# Vers_3_Moppy_Board.net
KiCad netlist of a schematic drawn in EAGLE
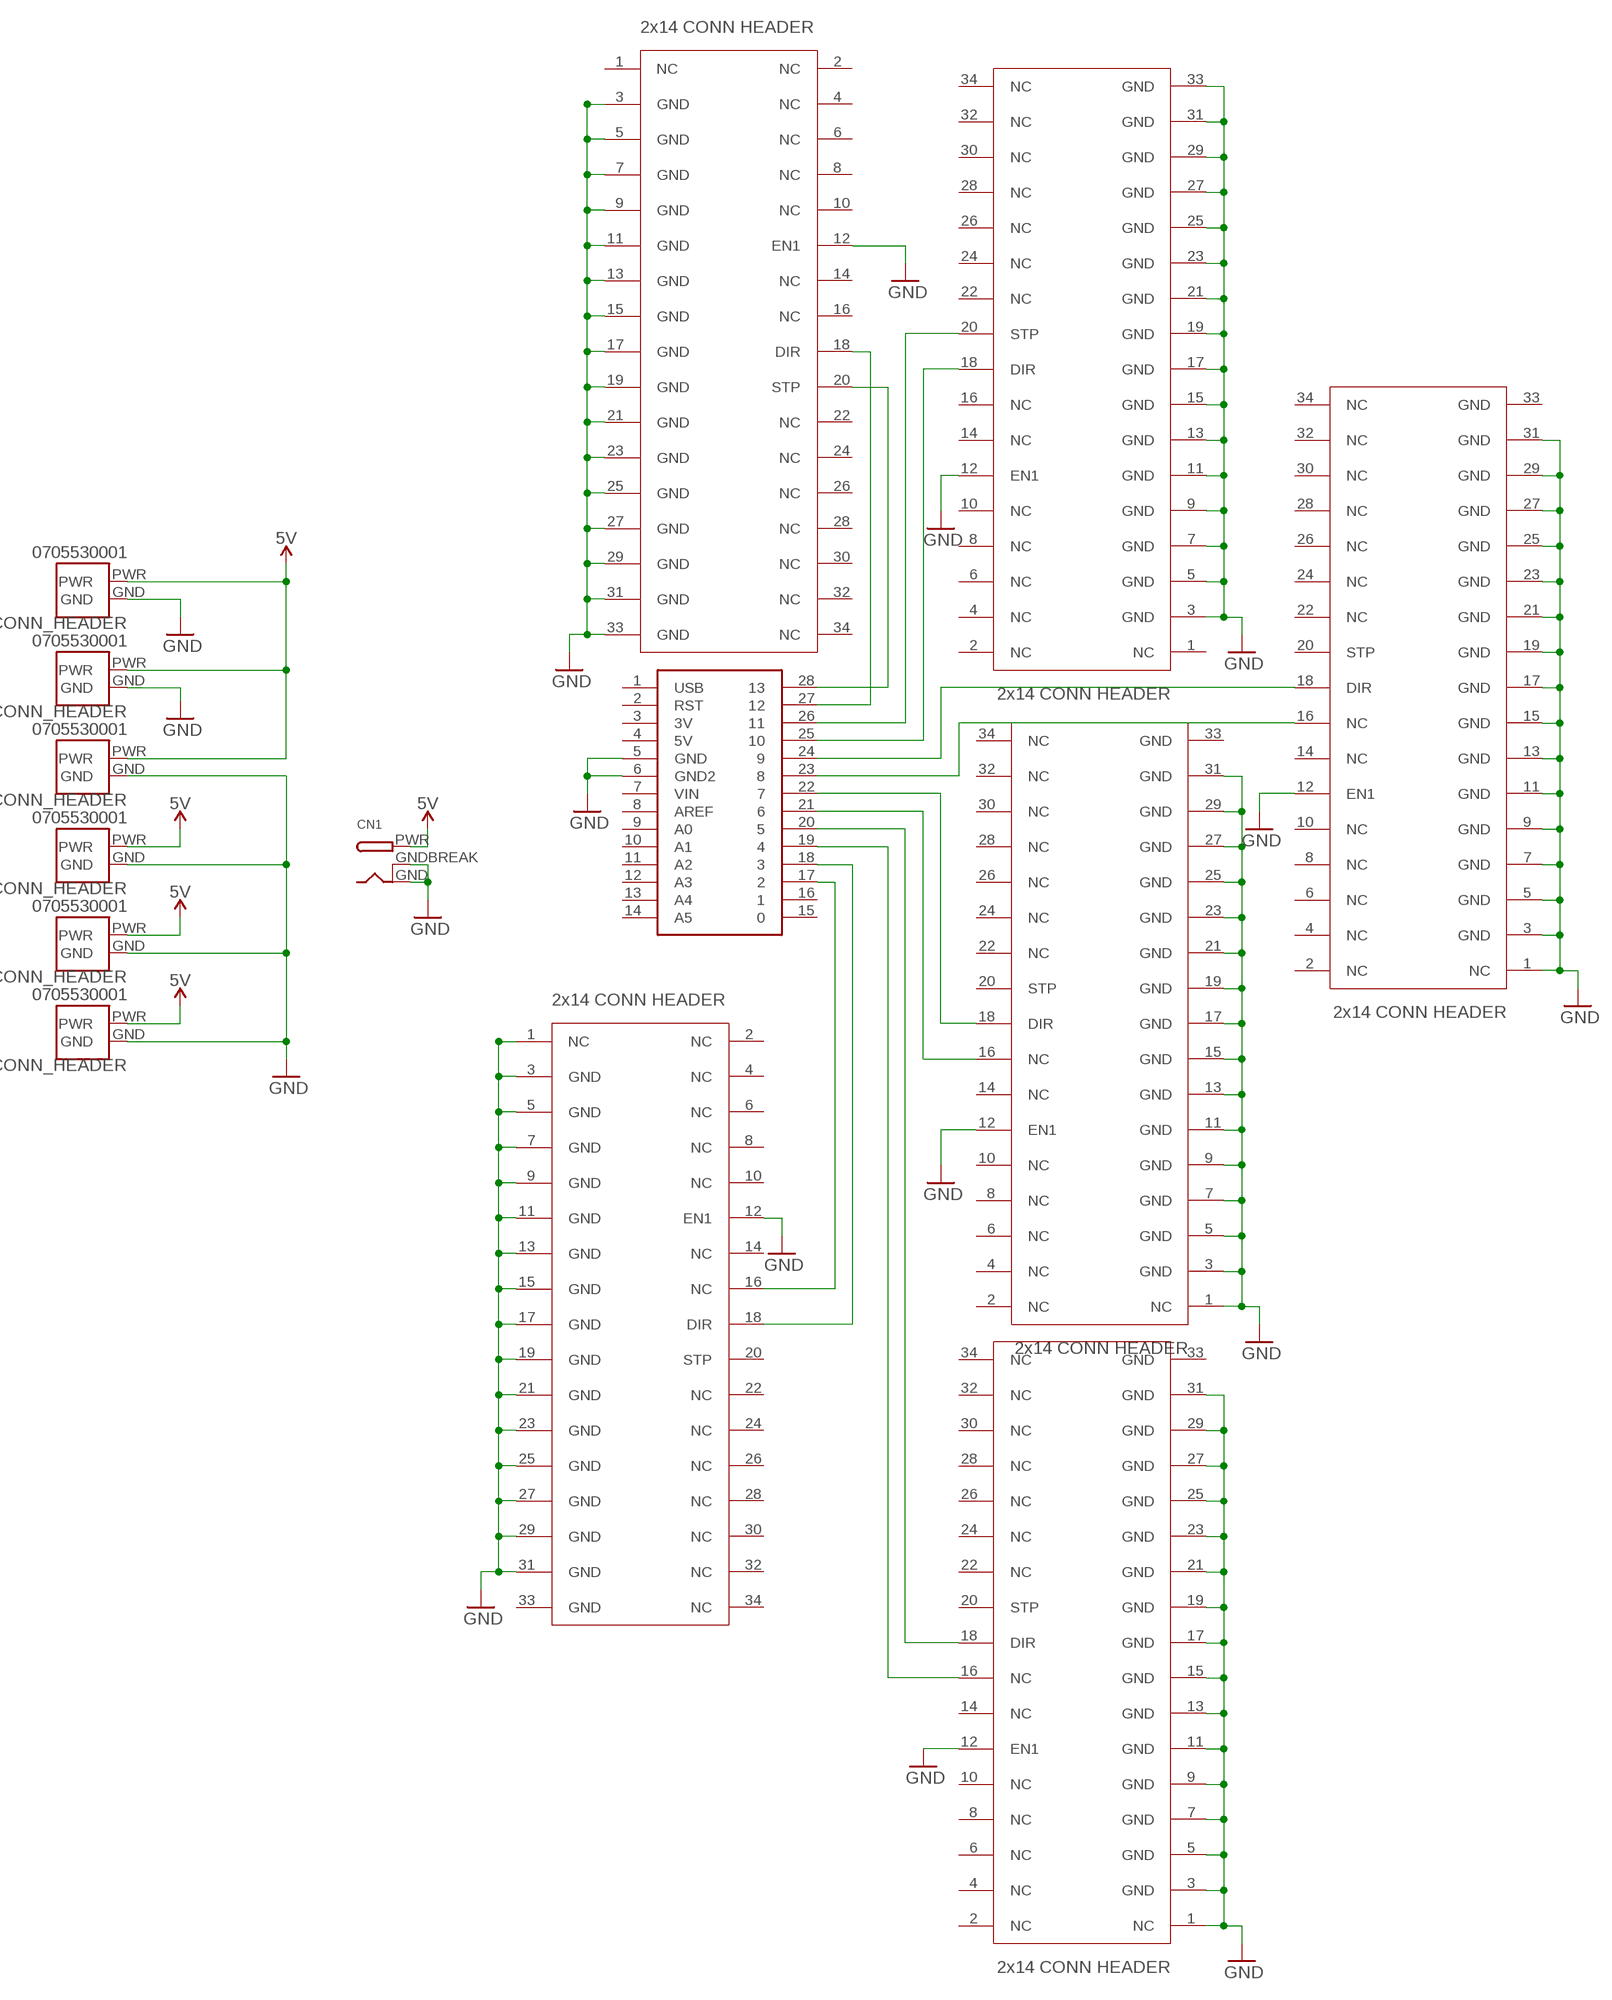
[diagram p0: schematic, sheet 1]

(export (version "E")
  (design (tool "Eeschema 10.0.6"))
  (components
    (comp (ref "CN1")
      (value "DCBARRELPTH")
      (footprint "eagle-import:DCJACK_2MM_PTH")
      (libsource (lib "eagle-import") (part "DCBARRELPTH"))
    )
    (comp (ref "U$1")
      (value "2X14_CONN_HEADER")
      (footprint "eagle-import:2X17_CONN_HEADER")
      (libsource (lib "eagle-import") (part "2X14_CONN_HEADER"))
    )
    (comp (ref "U$2")
      (value "2X14_CONN_HEADER")
      (footprint "eagle-import:2X17_CONN_HEADER")
      (libsource (lib "eagle-import") (part "2X14_CONN_HEADER"))
    )
    (comp (ref "U$3")
      (value "2X14_CONN_HEADER")
      (footprint "eagle-import:2X17_CONN_HEADER")
      (libsource (lib "eagle-import") (part "2X14_CONN_HEADER"))
    )
    (comp (ref "U$4")
      (value "2X14_CONN_HEADER")
      (footprint "eagle-import:2X17_CONN_HEADER")
      (libsource (lib "eagle-import") (part "2X14_CONN_HEADER"))
    )
    (comp (ref "U$5")
      (value "2X14_CONN_HEADER")
      (footprint "eagle-import:2X17_CONN_HEADER")
      (libsource (lib "eagle-import") (part "2X14_CONN_HEADER"))
    )
    (comp (ref "U$6")
      (value "2X14_CONN_HEADER")
      (footprint "eagle-import:2X17_CONN_HEADER")
      (libsource (lib "eagle-import") (part "2X14_CONN_HEADER"))
    )
    (comp (ref "U$8")
      (value "METROMINI")
      (footprint "eagle-import:METROMINI")
      (libsource (lib "eagle-import") (part "METROMINI"))
    )
    (comp (ref "X1")
      (value "0705530001")
      (footprint "eagle-import:MOLEX_0705530001")
      (fields (field (name "DIGI-KEY_PART_NUMBER") "WM4900-ND") (field (name "MF") "Molex"))
      (libsource (lib "eagle-import") (part "0705530001"))
    )
    (comp (ref "X2")
      (value "0705530001")
      (footprint "eagle-import:MOLEX_0705530001")
      (fields (field (name "DIGI-KEY_PART_NUMBER") "WM4900-ND") (field (name "MF") "Molex"))
      (libsource (lib "eagle-import") (part "0705530001"))
    )
    (comp (ref "X3")
      (value "0705530001")
      (footprint "eagle-import:MOLEX_0705530001")
      (fields (field (name "DIGI-KEY_PART_NUMBER") "WM4900-ND") (field (name "MF") "Molex"))
      (libsource (lib "eagle-import") (part "0705530001"))
    )
    (comp (ref "X4")
      (value "0705530001")
      (footprint "eagle-import:MOLEX_0705530001")
      (fields (field (name "DIGI-KEY_PART_NUMBER") "WM4900-ND") (field (name "MF") "Molex"))
      (libsource (lib "eagle-import") (part "0705530001"))
    )
    (comp (ref "X5")
      (value "0705530001")
      (footprint "eagle-import:MOLEX_0705530001")
      (fields (field (name "DIGI-KEY_PART_NUMBER") "WM4900-ND") (field (name "MF") "Molex"))
      (libsource (lib "eagle-import") (part "0705530001"))
    )
    (comp (ref "X6")
      (value "0705530001")
      (footprint "eagle-import:MOLEX_0705530001")
      (fields (field (name "DIGI-KEY_PART_NUMBER") "WM4900-ND") (field (name "MF") "Molex"))
      (libsource (lib "eagle-import") (part "0705530001"))
    )
  )
  (nets
    (net (code "1") (name "5V") (class "Default")
      (node (ref "CN1") (pin "PWR") (pinfunction "PWR_PWR") (pintype "power_in"))
      (node (ref "X1") (pin "PWR") (pinfunction "PWR_PWR") (pintype "passive"))
      (node (ref "X2") (pin "PWR") (pinfunction "PWR_PWR") (pintype "passive"))
      (node (ref "X3") (pin "PWR") (pinfunction "PWR_PWR") (pintype "passive"))
      (node (ref "X4") (pin "PWR") (pinfunction "PWR_PWR") (pintype "passive"))
      (node (ref "X5") (pin "PWR") (pinfunction "PWR_PWR") (pintype "passive"))
      (node (ref "X6") (pin "PWR") (pinfunction "PWR_PWR") (pintype "passive"))
    )
    (net (code "2") (name "GND") (class "Default")
      (node (ref "CN1") (pin "GND") (pinfunction "GND_GND") (pintype "power_in"))
      (node (ref "CN1") (pin "GNDBREAK") (pinfunction "GNDBREAK_GNDBREAK") (pintype "power_in"))
      (node (ref "U$1") (pin "1") (pinfunction "NC_1") (pintype "bidirectional"))
      (node (ref "U$1") (pin "11") (pinfunction "GND_11") (pintype "bidirectional"))
      (node (ref "U$1") (pin "12") (pinfunction "EN1_12") (pintype "bidirectional"))
      (node (ref "U$1") (pin "13") (pinfunction "GND_13") (pintype "bidirectional"))
      (node (ref "U$1") (pin "15") (pinfunction "GND_15") (pintype "bidirectional"))
      (node (ref "U$1") (pin "17") (pinfunction "GND_17") (pintype "bidirectional"))
      (node (ref "U$1") (pin "19") (pinfunction "GND_19") (pintype "bidirectional"))
      (node (ref "U$1") (pin "21") (pinfunction "GND_21") (pintype "bidirectional"))
      (node (ref "U$1") (pin "23") (pinfunction "GND_23") (pintype "bidirectional"))
      (node (ref "U$1") (pin "25") (pinfunction "GND_25") (pintype "bidirectional"))
      (node (ref "U$1") (pin "27") (pinfunction "GND_27") (pintype "bidirectional"))
      (node (ref "U$1") (pin "29") (pinfunction "GND_29") (pintype "bidirectional"))
      (node (ref "U$1") (pin "3") (pinfunction "GND_3") (pintype "bidirectional"))
      (node (ref "U$1") (pin "31") (pinfunction "GND_31") (pintype "bidirectional"))
      (node (ref "U$1") (pin "5") (pinfunction "GND_5") (pintype "bidirectional"))
      (node (ref "U$1") (pin "7") (pinfunction "GND_7") (pintype "bidirectional"))
      (node (ref "U$1") (pin "9") (pinfunction "GND_9") (pintype "bidirectional"))
      (node (ref "U$2") (pin "11") (pinfunction "GND_11") (pintype "bidirectional"))
      (node (ref "U$2") (pin "12") (pinfunction "EN1_12") (pintype "bidirectional"))
      (node (ref "U$2") (pin "13") (pinfunction "GND_13") (pintype "bidirectional"))
      (node (ref "U$2") (pin "15") (pinfunction "GND_15") (pintype "bidirectional"))
      (node (ref "U$2") (pin "17") (pinfunction "GND_17") (pintype "bidirectional"))
      (node (ref "U$2") (pin "19") (pinfunction "GND_19") (pintype "bidirectional"))
      (node (ref "U$2") (pin "21") (pinfunction "GND_21") (pintype "bidirectional"))
      (node (ref "U$2") (pin "23") (pinfunction "GND_23") (pintype "bidirectional"))
      (node (ref "U$2") (pin "25") (pinfunction "GND_25") (pintype "bidirectional"))
      (node (ref "U$2") (pin "27") (pinfunction "GND_27") (pintype "bidirectional"))
      (node (ref "U$2") (pin "29") (pinfunction "GND_29") (pintype "bidirectional"))
      (node (ref "U$2") (pin "3") (pinfunction "GND_3") (pintype "bidirectional"))
      (node (ref "U$2") (pin "31") (pinfunction "GND_31") (pintype "bidirectional"))
      (node (ref "U$2") (pin "33") (pinfunction "GND_33") (pintype "bidirectional"))
      (node (ref "U$2") (pin "5") (pinfunction "GND_5") (pintype "bidirectional"))
      (node (ref "U$2") (pin "7") (pinfunction "GND_7") (pintype "bidirectional"))
      (node (ref "U$2") (pin "9") (pinfunction "GND_9") (pintype "bidirectional"))
      (node (ref "U$3") (pin "11") (pinfunction "GND_11") (pintype "bidirectional"))
      (node (ref "U$3") (pin "12") (pinfunction "EN1_12") (pintype "bidirectional"))
      (node (ref "U$3") (pin "13") (pinfunction "GND_13") (pintype "bidirectional"))
      (node (ref "U$3") (pin "15") (pinfunction "GND_15") (pintype "bidirectional"))
      (node (ref "U$3") (pin "17") (pinfunction "GND_17") (pintype "bidirectional"))
      (node (ref "U$3") (pin "19") (pinfunction "GND_19") (pintype "bidirectional"))
      (node (ref "U$3") (pin "21") (pinfunction "GND_21") (pintype "bidirectional"))
      (node (ref "U$3") (pin "23") (pinfunction "GND_23") (pintype "bidirectional"))
      (node (ref "U$3") (pin "25") (pinfunction "GND_25") (pintype "bidirectional"))
      (node (ref "U$3") (pin "27") (pinfunction "GND_27") (pintype "bidirectional"))
      (node (ref "U$3") (pin "29") (pinfunction "GND_29") (pintype "bidirectional"))
      (node (ref "U$3") (pin "3") (pinfunction "GND_3") (pintype "bidirectional"))
      (node (ref "U$3") (pin "31") (pinfunction "GND_31") (pintype "bidirectional"))
      (node (ref "U$3") (pin "33") (pinfunction "GND_33") (pintype "bidirectional"))
      (node (ref "U$3") (pin "5") (pinfunction "GND_5") (pintype "bidirectional"))
      (node (ref "U$3") (pin "7") (pinfunction "GND_7") (pintype "bidirectional"))
      (node (ref "U$3") (pin "9") (pinfunction "GND_9") (pintype "bidirectional"))
      (node (ref "U$4") (pin "1") (pinfunction "NC_1") (pintype "bidirectional"))
      (node (ref "U$4") (pin "11") (pinfunction "GND_11") (pintype "bidirectional"))
      (node (ref "U$4") (pin "12") (pinfunction "EN1_12") (pintype "bidirectional"))
      (node (ref "U$4") (pin "13") (pinfunction "GND_13") (pintype "bidirectional"))
      (node (ref "U$4") (pin "15") (pinfunction "GND_15") (pintype "bidirectional"))
      (node (ref "U$4") (pin "17") (pinfunction "GND_17") (pintype "bidirectional"))
      (node (ref "U$4") (pin "19") (pinfunction "GND_19") (pintype "bidirectional"))
      (node (ref "U$4") (pin "21") (pinfunction "GND_21") (pintype "bidirectional"))
      (node (ref "U$4") (pin "23") (pinfunction "GND_23") (pintype "bidirectional"))
      (node (ref "U$4") (pin "25") (pinfunction "GND_25") (pintype "bidirectional"))
      (node (ref "U$4") (pin "27") (pinfunction "GND_27") (pintype "bidirectional"))
      (node (ref "U$4") (pin "29") (pinfunction "GND_29") (pintype "bidirectional"))
      (node (ref "U$4") (pin "3") (pinfunction "GND_3") (pintype "bidirectional"))
      (node (ref "U$4") (pin "31") (pinfunction "GND_31") (pintype "bidirectional"))
      (node (ref "U$4") (pin "5") (pinfunction "GND_5") (pintype "bidirectional"))
      (node (ref "U$4") (pin "7") (pinfunction "GND_7") (pintype "bidirectional"))
      (node (ref "U$4") (pin "9") (pinfunction "GND_9") (pintype "bidirectional"))
      (node (ref "U$5") (pin "1") (pinfunction "NC_1") (pintype "bidirectional"))
      (node (ref "U$5") (pin "11") (pinfunction "GND_11") (pintype "bidirectional"))
      (node (ref "U$5") (pin "12") (pinfunction "EN1_12") (pintype "bidirectional"))
      (node (ref "U$5") (pin "13") (pinfunction "GND_13") (pintype "bidirectional"))
      (node (ref "U$5") (pin "15") (pinfunction "GND_15") (pintype "bidirectional"))
      (node (ref "U$5") (pin "17") (pinfunction "GND_17") (pintype "bidirectional"))
      (node (ref "U$5") (pin "19") (pinfunction "GND_19") (pintype "bidirectional"))
      (node (ref "U$5") (pin "21") (pinfunction "GND_21") (pintype "bidirectional"))
      (node (ref "U$5") (pin "23") (pinfunction "GND_23") (pintype "bidirectional"))
      (node (ref "U$5") (pin "25") (pinfunction "GND_25") (pintype "bidirectional"))
      (node (ref "U$5") (pin "27") (pinfunction "GND_27") (pintype "bidirectional"))
      (node (ref "U$5") (pin "29") (pinfunction "GND_29") (pintype "bidirectional"))
      (node (ref "U$5") (pin "3") (pinfunction "GND_3") (pintype "bidirectional"))
      (node (ref "U$5") (pin "31") (pinfunction "GND_31") (pintype "bidirectional"))
      (node (ref "U$5") (pin "5") (pinfunction "GND_5") (pintype "bidirectional"))
      (node (ref "U$5") (pin "7") (pinfunction "GND_7") (pintype "bidirectional"))
      (node (ref "U$5") (pin "9") (pinfunction "GND_9") (pintype "bidirectional"))
      (node (ref "U$6") (pin "1") (pinfunction "NC_1") (pintype "bidirectional"))
      (node (ref "U$6") (pin "11") (pinfunction "GND_11") (pintype "bidirectional"))
      (node (ref "U$6") (pin "12") (pinfunction "EN1_12") (pintype "bidirectional"))
      (node (ref "U$6") (pin "13") (pinfunction "GND_13") (pintype "bidirectional"))
      (node (ref "U$6") (pin "15") (pinfunction "GND_15") (pintype "bidirectional"))
      (node (ref "U$6") (pin "17") (pinfunction "GND_17") (pintype "bidirectional"))
      (node (ref "U$6") (pin "19") (pinfunction "GND_19") (pintype "bidirectional"))
      (node (ref "U$6") (pin "21") (pinfunction "GND_21") (pintype "bidirectional"))
      (node (ref "U$6") (pin "23") (pinfunction "GND_23") (pintype "bidirectional"))
      (node (ref "U$6") (pin "25") (pinfunction "GND_25") (pintype "bidirectional"))
      (node (ref "U$6") (pin "27") (pinfunction "GND_27") (pintype "bidirectional"))
      (node (ref "U$6") (pin "29") (pinfunction "GND_29") (pintype "bidirectional"))
      (node (ref "U$6") (pin "3") (pinfunction "GND_3") (pintype "bidirectional"))
      (node (ref "U$6") (pin "31") (pinfunction "GND_31") (pintype "bidirectional"))
      (node (ref "U$6") (pin "5") (pinfunction "GND_5") (pintype "bidirectional"))
      (node (ref "U$6") (pin "7") (pinfunction "GND_7") (pintype "bidirectional"))
      (node (ref "U$6") (pin "9") (pinfunction "GND_9") (pintype "bidirectional"))
      (node (ref "U$8") (pin "5") (pinfunction "GND_5") (pintype "bidirectional"))
      (node (ref "U$8") (pin "6") (pinfunction "GND2_6") (pintype "bidirectional"))
      (node (ref "X1") (pin "GND") (pinfunction "GND_GND") (pintype "passive"))
      (node (ref "X2") (pin "GND") (pinfunction "GND_GND") (pintype "passive"))
      (node (ref "X3") (pin "GND") (pinfunction "GND_GND") (pintype "passive"))
      (node (ref "X4") (pin "GND") (pinfunction "GND_GND") (pintype "passive"))
      (node (ref "X5") (pin "GND") (pinfunction "GND_GND") (pintype "passive"))
      (node (ref "X6") (pin "GND") (pinfunction "GND_GND") (pintype "passive"))
    )
    (net (code "3") (name "Net-(U$1-DIR)") (class "Default")
      (node (ref "U$1") (pin "18") (pinfunction "DIR_18") (pintype "bidirectional"))
      (node (ref "U$8") (pin "18") (pinfunction "3_18") (pintype "bidirectional"))
    )
    (net (code "4") (name "Net-(U$2-DIR)") (class "Default")
      (node (ref "U$2") (pin "18") (pinfunction "DIR_18") (pintype "bidirectional"))
      (node (ref "U$8") (pin "27") (pinfunction "12_27") (pintype "bidirectional"))
    )
    (net (code "5") (name "Net-(U$2-STP)") (class "Default")
      (node (ref "U$2") (pin "20") (pinfunction "STP_20") (pintype "bidirectional"))
      (node (ref "U$8") (pin "28") (pinfunction "13_28") (pintype "bidirectional"))
    )
    (net (code "6") (name "Net-(U$3-DIR)") (class "Default")
      (node (ref "U$3") (pin "18") (pinfunction "DIR_18") (pintype "bidirectional"))
      (node (ref "U$8") (pin "25") (pinfunction "10_25") (pintype "bidirectional"))
    )
    (net (code "7") (name "Net-(U$3-STP)") (class "Default")
      (node (ref "U$3") (pin "20") (pinfunction "STP_20") (pintype "bidirectional"))
      (node (ref "U$8") (pin "26") (pinfunction "11_26") (pintype "bidirectional"))
    )
    (net (code "8") (name "Net-(U$4-DIR)") (class "Default")
      (node (ref "U$4") (pin "18") (pinfunction "DIR_18") (pintype "bidirectional"))
      (node (ref "U$8") (pin "20") (pinfunction "5_20") (pintype "bidirectional"))
    )
    (net (code "9") (name "Net-(U$5-DIR)") (class "Default")
      (node (ref "U$5") (pin "18") (pinfunction "DIR_18") (pintype "bidirectional"))
      (node (ref "U$8") (pin "22") (pinfunction "7_22") (pintype "bidirectional"))
    )
    (net (code "10") (name "Net-(U$6-DIR)") (class "Default")
      (node (ref "U$6") (pin "18") (pinfunction "DIR_18") (pintype "bidirectional"))
      (node (ref "U$8") (pin "24") (pinfunction "9_24") (pintype "bidirectional"))
    )
    (net (code "11") (name "Net-(U$8-2)") (class "Default")
      (node (ref "U$1") (pin "16") (pinfunction "NC_16") (pintype "bidirectional"))
      (node (ref "U$8") (pin "17") (pinfunction "2_17") (pintype "bidirectional"))
    )
    (net (code "12") (name "Net-(U$8-4)") (class "Default")
      (node (ref "U$4") (pin "16") (pinfunction "NC_16") (pintype "bidirectional"))
      (node (ref "U$8") (pin "19") (pinfunction "4_19") (pintype "bidirectional"))
    )
    (net (code "13") (name "Net-(U$8-6)") (class "Default")
      (node (ref "U$5") (pin "16") (pinfunction "NC_16") (pintype "bidirectional"))
      (node (ref "U$8") (pin "21") (pinfunction "6_21") (pintype "bidirectional"))
    )
    (net (code "14") (name "Net-(U$8-8)") (class "Default")
      (node (ref "U$6") (pin "16") (pinfunction "NC_16") (pintype "bidirectional"))
      (node (ref "U$8") (pin "23") (pinfunction "8_23") (pintype "bidirectional"))
    )
    (net (code "15") (name "unconnected-(U$1-GND-Pad33)") (class "Default")
      (node (ref "U$1") (pin "33") (pinfunction "GND_33") (pintype "bidirectional"))
    )
    (net (code "16") (name "unconnected-(U$1-NC-Pad2)") (class "Default")
      (node (ref "U$1") (pin "2") (pinfunction "NC_2") (pintype "bidirectional"))
    )
    (net (code "17") (name "unconnected-(U$1-NC-Pad4)") (class "Default")
      (node (ref "U$1") (pin "4") (pinfunction "NC_4") (pintype "bidirectional"))
    )
    (net (code "18") (name "unconnected-(U$1-NC-Pad6)") (class "Default")
      (node (ref "U$1") (pin "6") (pinfunction "NC_6") (pintype "bidirectional"))
    )
    (net (code "19") (name "unconnected-(U$1-NC-Pad8)") (class "Default")
      (node (ref "U$1") (pin "8") (pinfunction "NC_8") (pintype "bidirectional"))
    )
    (net (code "20") (name "unconnected-(U$1-NC-Pad10)") (class "Default")
      (node (ref "U$1") (pin "10") (pinfunction "NC_10") (pintype "bidirectional"))
    )
    (net (code "21") (name "unconnected-(U$1-NC-Pad14)") (class "Default")
      (node (ref "U$1") (pin "14") (pinfunction "NC_14") (pintype "bidirectional"))
    )
    (net (code "22") (name "unconnected-(U$1-NC-Pad22)") (class "Default")
      (node (ref "U$1") (pin "22") (pinfunction "NC_22") (pintype "bidirectional"))
    )
    (net (code "23") (name "unconnected-(U$1-NC-Pad24)") (class "Default")
      (node (ref "U$1") (pin "24") (pinfunction "NC_24") (pintype "bidirectional"))
    )
    (net (code "24") (name "unconnected-(U$1-NC-Pad26)") (class "Default")
      (node (ref "U$1") (pin "26") (pinfunction "NC_26") (pintype "bidirectional"))
    )
    (net (code "25") (name "unconnected-(U$1-NC-Pad28)") (class "Default")
      (node (ref "U$1") (pin "28") (pinfunction "NC_28") (pintype "bidirectional"))
    )
    (net (code "26") (name "unconnected-(U$1-NC-Pad30)") (class "Default")
      (node (ref "U$1") (pin "30") (pinfunction "NC_30") (pintype "bidirectional"))
    )
    (net (code "27") (name "unconnected-(U$1-NC-Pad32)") (class "Default")
      (node (ref "U$1") (pin "32") (pinfunction "NC_32") (pintype "bidirectional"))
    )
    (net (code "28") (name "unconnected-(U$1-NC-Pad34)") (class "Default")
      (node (ref "U$1") (pin "34") (pinfunction "NC_34") (pintype "bidirectional"))
    )
    (net (code "29") (name "unconnected-(U$1-STP-Pad20)") (class "Default")
      (node (ref "U$1") (pin "20") (pinfunction "STP_20") (pintype "bidirectional"))
    )
    (net (code "30") (name "unconnected-(U$2-NC-Pad1)") (class "Default")
      (node (ref "U$2") (pin "1") (pinfunction "NC_1") (pintype "bidirectional"))
    )
    (net (code "31") (name "unconnected-(U$2-NC-Pad2)") (class "Default")
      (node (ref "U$2") (pin "2") (pinfunction "NC_2") (pintype "bidirectional"))
    )
    (net (code "32") (name "unconnected-(U$2-NC-Pad4)") (class "Default")
      (node (ref "U$2") (pin "4") (pinfunction "NC_4") (pintype "bidirectional"))
    )
    (net (code "33") (name "unconnected-(U$2-NC-Pad6)") (class "Default")
      (node (ref "U$2") (pin "6") (pinfunction "NC_6") (pintype "bidirectional"))
    )
    (net (code "34") (name "unconnected-(U$2-NC-Pad8)") (class "Default")
      (node (ref "U$2") (pin "8") (pinfunction "NC_8") (pintype "bidirectional"))
    )
    (net (code "35") (name "unconnected-(U$2-NC-Pad10)") (class "Default")
      (node (ref "U$2") (pin "10") (pinfunction "NC_10") (pintype "bidirectional"))
    )
    (net (code "36") (name "unconnected-(U$2-NC-Pad14)") (class "Default")
      (node (ref "U$2") (pin "14") (pinfunction "NC_14") (pintype "bidirectional"))
    )
    (net (code "37") (name "unconnected-(U$2-NC-Pad16)") (class "Default")
      (node (ref "U$2") (pin "16") (pinfunction "NC_16") (pintype "bidirectional"))
    )
    (net (code "38") (name "unconnected-(U$2-NC-Pad22)") (class "Default")
      (node (ref "U$2") (pin "22") (pinfunction "NC_22") (pintype "bidirectional"))
    )
    (net (code "39") (name "unconnected-(U$2-NC-Pad24)") (class "Default")
      (node (ref "U$2") (pin "24") (pinfunction "NC_24") (pintype "bidirectional"))
    )
    (net (code "40") (name "unconnected-(U$2-NC-Pad26)") (class "Default")
      (node (ref "U$2") (pin "26") (pinfunction "NC_26") (pintype "bidirectional"))
    )
    (net (code "41") (name "unconnected-(U$2-NC-Pad28)") (class "Default")
      (node (ref "U$2") (pin "28") (pinfunction "NC_28") (pintype "bidirectional"))
    )
    (net (code "42") (name "unconnected-(U$2-NC-Pad30)") (class "Default")
      (node (ref "U$2") (pin "30") (pinfunction "NC_30") (pintype "bidirectional"))
    )
    (net (code "43") (name "unconnected-(U$2-NC-Pad32)") (class "Default")
      (node (ref "U$2") (pin "32") (pinfunction "NC_32") (pintype "bidirectional"))
    )
    (net (code "44") (name "unconnected-(U$2-NC-Pad34)") (class "Default")
      (node (ref "U$2") (pin "34") (pinfunction "NC_34") (pintype "bidirectional"))
    )
    (net (code "45") (name "unconnected-(U$3-NC-Pad1)") (class "Default")
      (node (ref "U$3") (pin "1") (pinfunction "NC_1") (pintype "bidirectional"))
    )
    (net (code "46") (name "unconnected-(U$3-NC-Pad2)") (class "Default")
      (node (ref "U$3") (pin "2") (pinfunction "NC_2") (pintype "bidirectional"))
    )
    (net (code "47") (name "unconnected-(U$3-NC-Pad4)") (class "Default")
      (node (ref "U$3") (pin "4") (pinfunction "NC_4") (pintype "bidirectional"))
    )
    (net (code "48") (name "unconnected-(U$3-NC-Pad6)") (class "Default")
      (node (ref "U$3") (pin "6") (pinfunction "NC_6") (pintype "bidirectional"))
    )
    (net (code "49") (name "unconnected-(U$3-NC-Pad8)") (class "Default")
      (node (ref "U$3") (pin "8") (pinfunction "NC_8") (pintype "bidirectional"))
    )
    (net (code "50") (name "unconnected-(U$3-NC-Pad10)") (class "Default")
      (node (ref "U$3") (pin "10") (pinfunction "NC_10") (pintype "bidirectional"))
    )
    (net (code "51") (name "unconnected-(U$3-NC-Pad14)") (class "Default")
      (node (ref "U$3") (pin "14") (pinfunction "NC_14") (pintype "bidirectional"))
    )
    (net (code "52") (name "unconnected-(U$3-NC-Pad16)") (class "Default")
      (node (ref "U$3") (pin "16") (pinfunction "NC_16") (pintype "bidirectional"))
    )
    (net (code "53") (name "unconnected-(U$3-NC-Pad22)") (class "Default")
      (node (ref "U$3") (pin "22") (pinfunction "NC_22") (pintype "bidirectional"))
    )
    (net (code "54") (name "unconnected-(U$3-NC-Pad24)") (class "Default")
      (node (ref "U$3") (pin "24") (pinfunction "NC_24") (pintype "bidirectional"))
    )
    (net (code "55") (name "unconnected-(U$3-NC-Pad26)") (class "Default")
      (node (ref "U$3") (pin "26") (pinfunction "NC_26") (pintype "bidirectional"))
    )
    (net (code "56") (name "unconnected-(U$3-NC-Pad28)") (class "Default")
      (node (ref "U$3") (pin "28") (pinfunction "NC_28") (pintype "bidirectional"))
    )
    (net (code "57") (name "unconnected-(U$3-NC-Pad30)") (class "Default")
      (node (ref "U$3") (pin "30") (pinfunction "NC_30") (pintype "bidirectional"))
    )
    (net (code "58") (name "unconnected-(U$3-NC-Pad32)") (class "Default")
      (node (ref "U$3") (pin "32") (pinfunction "NC_32") (pintype "bidirectional"))
    )
    (net (code "59") (name "unconnected-(U$3-NC-Pad34)") (class "Default")
      (node (ref "U$3") (pin "34") (pinfunction "NC_34") (pintype "bidirectional"))
    )
    (net (code "60") (name "unconnected-(U$4-GND-Pad33)") (class "Default")
      (node (ref "U$4") (pin "33") (pinfunction "GND_33") (pintype "bidirectional"))
    )
    (net (code "61") (name "unconnected-(U$4-NC-Pad2)") (class "Default")
      (node (ref "U$4") (pin "2") (pinfunction "NC_2") (pintype "bidirectional"))
    )
    (net (code "62") (name "unconnected-(U$4-NC-Pad4)") (class "Default")
      (node (ref "U$4") (pin "4") (pinfunction "NC_4") (pintype "bidirectional"))
    )
    (net (code "63") (name "unconnected-(U$4-NC-Pad6)") (class "Default")
      (node (ref "U$4") (pin "6") (pinfunction "NC_6") (pintype "bidirectional"))
    )
    (net (code "64") (name "unconnected-(U$4-NC-Pad8)") (class "Default")
      (node (ref "U$4") (pin "8") (pinfunction "NC_8") (pintype "bidirectional"))
    )
    (net (code "65") (name "unconnected-(U$4-NC-Pad10)") (class "Default")
      (node (ref "U$4") (pin "10") (pinfunction "NC_10") (pintype "bidirectional"))
    )
    (net (code "66") (name "unconnected-(U$4-NC-Pad14)") (class "Default")
      (node (ref "U$4") (pin "14") (pinfunction "NC_14") (pintype "bidirectional"))
    )
    (net (code "67") (name "unconnected-(U$4-NC-Pad22)") (class "Default")
      (node (ref "U$4") (pin "22") (pinfunction "NC_22") (pintype "bidirectional"))
    )
    (net (code "68") (name "unconnected-(U$4-NC-Pad24)") (class "Default")
      (node (ref "U$4") (pin "24") (pinfunction "NC_24") (pintype "bidirectional"))
    )
    (net (code "69") (name "unconnected-(U$4-NC-Pad26)") (class "Default")
      (node (ref "U$4") (pin "26") (pinfunction "NC_26") (pintype "bidirectional"))
    )
    (net (code "70") (name "unconnected-(U$4-NC-Pad28)") (class "Default")
      (node (ref "U$4") (pin "28") (pinfunction "NC_28") (pintype "bidirectional"))
    )
    (net (code "71") (name "unconnected-(U$4-NC-Pad30)") (class "Default")
      (node (ref "U$4") (pin "30") (pinfunction "NC_30") (pintype "bidirectional"))
    )
    (net (code "72") (name "unconnected-(U$4-NC-Pad32)") (class "Default")
      (node (ref "U$4") (pin "32") (pinfunction "NC_32") (pintype "bidirectional"))
    )
    (net (code "73") (name "unconnected-(U$4-NC-Pad34)") (class "Default")
      (node (ref "U$4") (pin "34") (pinfunction "NC_34") (pintype "bidirectional"))
    )
    (net (code "74") (name "unconnected-(U$4-STP-Pad20)") (class "Default")
      (node (ref "U$4") (pin "20") (pinfunction "STP_20") (pintype "bidirectional"))
    )
    (net (code "75") (name "unconnected-(U$5-GND-Pad33)") (class "Default")
      (node (ref "U$5") (pin "33") (pinfunction "GND_33") (pintype "bidirectional"))
    )
    (net (code "76") (name "unconnected-(U$5-NC-Pad2)") (class "Default")
      (node (ref "U$5") (pin "2") (pinfunction "NC_2") (pintype "bidirectional"))
    )
    (net (code "77") (name "unconnected-(U$5-NC-Pad4)") (class "Default")
      (node (ref "U$5") (pin "4") (pinfunction "NC_4") (pintype "bidirectional"))
    )
    (net (code "78") (name "unconnected-(U$5-NC-Pad6)") (class "Default")
      (node (ref "U$5") (pin "6") (pinfunction "NC_6") (pintype "bidirectional"))
    )
    (net (code "79") (name "unconnected-(U$5-NC-Pad8)") (class "Default")
      (node (ref "U$5") (pin "8") (pinfunction "NC_8") (pintype "bidirectional"))
    )
    (net (code "80") (name "unconnected-(U$5-NC-Pad10)") (class "Default")
      (node (ref "U$5") (pin "10") (pinfunction "NC_10") (pintype "bidirectional"))
    )
    (net (code "81") (name "unconnected-(U$5-NC-Pad14)") (class "Default")
      (node (ref "U$5") (pin "14") (pinfunction "NC_14") (pintype "bidirectional"))
    )
    (net (code "82") (name "unconnected-(U$5-NC-Pad22)") (class "Default")
      (node (ref "U$5") (pin "22") (pinfunction "NC_22") (pintype "bidirectional"))
    )
    (net (code "83") (name "unconnected-(U$5-NC-Pad24)") (class "Default")
      (node (ref "U$5") (pin "24") (pinfunction "NC_24") (pintype "bidirectional"))
    )
    (net (code "84") (name "unconnected-(U$5-NC-Pad26)") (class "Default")
      (node (ref "U$5") (pin "26") (pinfunction "NC_26") (pintype "bidirectional"))
    )
    (net (code "85") (name "unconnected-(U$5-NC-Pad28)") (class "Default")
      (node (ref "U$5") (pin "28") (pinfunction "NC_28") (pintype "bidirectional"))
    )
    (net (code "86") (name "unconnected-(U$5-NC-Pad30)") (class "Default")
      (node (ref "U$5") (pin "30") (pinfunction "NC_30") (pintype "bidirectional"))
    )
    (net (code "87") (name "unconnected-(U$5-NC-Pad32)") (class "Default")
      (node (ref "U$5") (pin "32") (pinfunction "NC_32") (pintype "bidirectional"))
    )
    (net (code "88") (name "unconnected-(U$5-NC-Pad34)") (class "Default")
      (node (ref "U$5") (pin "34") (pinfunction "NC_34") (pintype "bidirectional"))
    )
    (net (code "89") (name "unconnected-(U$5-STP-Pad20)") (class "Default")
      (node (ref "U$5") (pin "20") (pinfunction "STP_20") (pintype "bidirectional"))
    )
    (net (code "90") (name "unconnected-(U$6-GND-Pad33)") (class "Default")
      (node (ref "U$6") (pin "33") (pinfunction "GND_33") (pintype "bidirectional"))
    )
    (net (code "91") (name "unconnected-(U$6-NC-Pad2)") (class "Default")
      (node (ref "U$6") (pin "2") (pinfunction "NC_2") (pintype "bidirectional"))
    )
    (net (code "92") (name "unconnected-(U$6-NC-Pad4)") (class "Default")
      (node (ref "U$6") (pin "4") (pinfunction "NC_4") (pintype "bidirectional"))
    )
    (net (code "93") (name "unconnected-(U$6-NC-Pad6)") (class "Default")
      (node (ref "U$6") (pin "6") (pinfunction "NC_6") (pintype "bidirectional"))
    )
    (net (code "94") (name "unconnected-(U$6-NC-Pad8)") (class "Default")
      (node (ref "U$6") (pin "8") (pinfunction "NC_8") (pintype "bidirectional"))
    )
    (net (code "95") (name "unconnected-(U$6-NC-Pad10)") (class "Default")
      (node (ref "U$6") (pin "10") (pinfunction "NC_10") (pintype "bidirectional"))
    )
    (net (code "96") (name "unconnected-(U$6-NC-Pad14)") (class "Default")
      (node (ref "U$6") (pin "14") (pinfunction "NC_14") (pintype "bidirectional"))
    )
    (net (code "97") (name "unconnected-(U$6-NC-Pad22)") (class "Default")
      (node (ref "U$6") (pin "22") (pinfunction "NC_22") (pintype "bidirectional"))
    )
    (net (code "98") (name "unconnected-(U$6-NC-Pad24)") (class "Default")
      (node (ref "U$6") (pin "24") (pinfunction "NC_24") (pintype "bidirectional"))
    )
    (net (code "99") (name "unconnected-(U$6-NC-Pad26)") (class "Default")
      (node (ref "U$6") (pin "26") (pinfunction "NC_26") (pintype "bidirectional"))
    )
    (net (code "100") (name "unconnected-(U$6-NC-Pad28)") (class "Default")
      (node (ref "U$6") (pin "28") (pinfunction "NC_28") (pintype "bidirectional"))
    )
    (net (code "101") (name "unconnected-(U$6-NC-Pad30)") (class "Default")
      (node (ref "U$6") (pin "30") (pinfunction "NC_30") (pintype "bidirectional"))
    )
    (net (code "102") (name "unconnected-(U$6-NC-Pad32)") (class "Default")
      (node (ref "U$6") (pin "32") (pinfunction "NC_32") (pintype "bidirectional"))
    )
    (net (code "103") (name "unconnected-(U$6-NC-Pad34)") (class "Default")
      (node (ref "U$6") (pin "34") (pinfunction "NC_34") (pintype "bidirectional"))
    )
    (net (code "104") (name "unconnected-(U$6-STP-Pad20)") (class "Default")
      (node (ref "U$6") (pin "20") (pinfunction "STP_20") (pintype "bidirectional"))
    )
    (net (code "105") (name "unconnected-(U$8-0-Pad15)") (class "Default")
      (node (ref "U$8") (pin "15") (pinfunction "0_15") (pintype "bidirectional"))
    )
    (net (code "106") (name "unconnected-(U$8-1-Pad16)") (class "Default")
      (node (ref "U$8") (pin "16") (pinfunction "1_16") (pintype "bidirectional"))
    )
    (net (code "107") (name "unconnected-(U$8-3V-Pad3)") (class "Default")
      (node (ref "U$8") (pin "3") (pinfunction "3V_3") (pintype "bidirectional"))
    )
    (net (code "108") (name "unconnected-(U$8-5V-Pad4)") (class "Default")
      (node (ref "U$8") (pin "4") (pinfunction "5V_4") (pintype "bidirectional"))
    )
    (net (code "109") (name "unconnected-(U$8-A0-Pad9)") (class "Default")
      (node (ref "U$8") (pin "9") (pinfunction "A0_9") (pintype "bidirectional"))
    )
    (net (code "110") (name "unconnected-(U$8-A1-Pad10)") (class "Default")
      (node (ref "U$8") (pin "10") (pinfunction "A1_10") (pintype "bidirectional"))
    )
    (net (code "111") (name "unconnected-(U$8-A2-Pad11)") (class "Default")
      (node (ref "U$8") (pin "11") (pinfunction "A2_11") (pintype "bidirectional"))
    )
    (net (code "112") (name "unconnected-(U$8-A3-Pad12)") (class "Default")
      (node (ref "U$8") (pin "12") (pinfunction "A3_12") (pintype "bidirectional"))
    )
    (net (code "113") (name "unconnected-(U$8-A4-Pad13)") (class "Default")
      (node (ref "U$8") (pin "13") (pinfunction "A4_13") (pintype "bidirectional"))
    )
    (net (code "114") (name "unconnected-(U$8-A5-Pad14)") (class "Default")
      (node (ref "U$8") (pin "14") (pinfunction "A5_14") (pintype "bidirectional"))
    )
    (net (code "115") (name "unconnected-(U$8-AREF-Pad8)") (class "Default")
      (node (ref "U$8") (pin "8") (pinfunction "AREF_8") (pintype "bidirectional"))
    )
    (net (code "116") (name "unconnected-(U$8-RST-Pad2)") (class "Default")
      (node (ref "U$8") (pin "2") (pinfunction "RST_2") (pintype "bidirectional"))
    )
    (net (code "117") (name "unconnected-(U$8-USB-Pad1)") (class "Default")
      (node (ref "U$8") (pin "1") (pinfunction "USB_1") (pintype "bidirectional"))
    )
    (net (code "118") (name "unconnected-(U$8-VIN-Pad7)") (class "Default")
      (node (ref "U$8") (pin "7") (pinfunction "VIN_7") (pintype "bidirectional"))
    )
  )
)
